# nodemcu.net
KiCad netlist of a schematic drawn in EAGLE
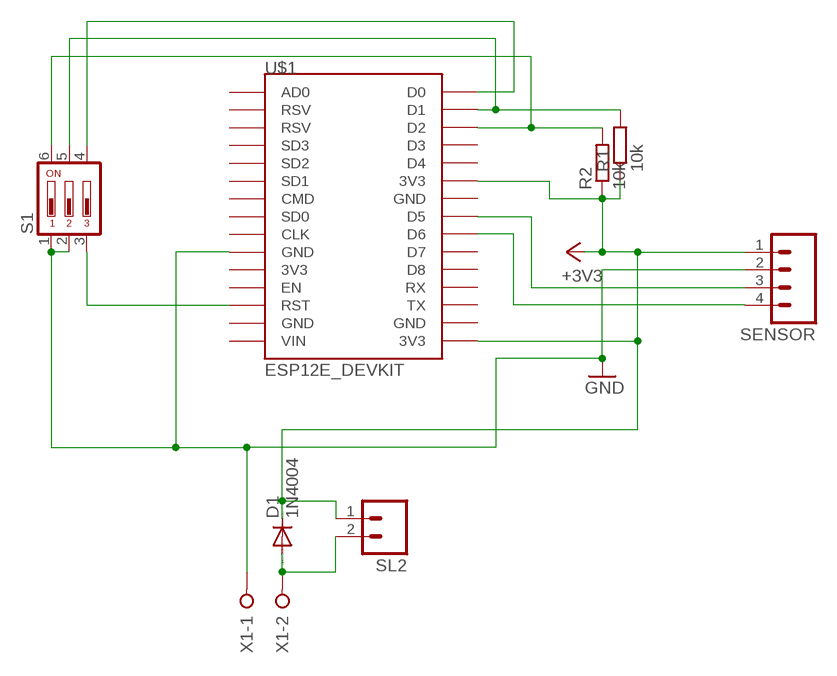
[diagram p0: schematic, sheet 1]

(export (version "E")
  (design (tool "Eeschema 10.0.6"))
  (components
    (comp (ref "D1")
      (value "1N4004")
      (footprint "eagle-import:DO41-10")
      (libsource (lib "eagle-import") (part "1N4004"))
    )
    (comp (ref "R1")
      (value "10k")
      (footprint "eagle-import:0207_10")
      (libsource (lib "eagle-import") (part "R-EU_0207/10"))
    )
    (comp (ref "R2")
      (value "10k")
      (footprint "eagle-import:0207_10")
      (libsource (lib "eagle-import") (part "R-EU_0207/10"))
    )
    (comp (ref "S1")
      (value "DIP03YL")
      (footprint "eagle-import:DIP03YL")
      (libsource (lib "eagle-import") (part "DIP03YL"))
    )
    (comp (ref "SENSOR")
      (value "M04")
      (footprint "eagle-import:04P")
      (libsource (lib "eagle-import") (part "M04"))
    )
    (comp (ref "SL2")
      (value "M02")
      (footprint "eagle-import:02P")
      (libsource (lib "eagle-import") (part "M02"))
    )
    (comp (ref "U$1")
      (value "ESP12E_DEVKIT")
      (footprint "eagle-import:ESP12E_DEVKIT")
      (libsource (lib "eagle-import") (part "ESP12E_DEVKIT"))
    )
    (comp (ref "X1")
      (value "W237-02P")
      (footprint "eagle-import:W237-132")
      (libsource (lib "eagle-import") (part "W237-02P"))
    )
  )
  (nets
    (net (code "1") (name "+3V3") (class "Default")
      (node (ref "D1") (pin "C") (pinfunction "C_C") (pintype "passive"))
      (node (ref "R1") (pin "1") (pinfunction "1_1") (pintype "passive"))
      (node (ref "R2") (pin "1") (pinfunction "1_1") (pintype "passive"))
      (node (ref "SENSOR") (pin "1") (pinfunction "1_1") (pintype "passive"))
      (node (ref "SL2") (pin "1") (pinfunction "1_1") (pintype "passive"))
      (node (ref "U$1") (pin "3V3@1") (pinfunction "3V3_3V3@1") (pintype "bidirectional"))
      (node (ref "U$1") (pin "3V3@2") (pinfunction "3V3_3V3@2") (pintype "bidirectional"))
    )
    (net (code "2") (name "GND") (class "Default")
      (node (ref "S1") (pin "1") (pinfunction "1_1") (pintype "passive"))
      (node (ref "S1") (pin "2") (pinfunction "2_2") (pintype "passive"))
      (node (ref "SENSOR") (pin "2") (pinfunction "2_2") (pintype "passive"))
      (node (ref "U$1") (pin "GND@0") (pinfunction "GND_GND@0") (pintype "bidirectional"))
      (node (ref "X1") (pin "1") (pinfunction "KL_1") (pintype "passive"))
    )
    (net (code "3") (name "Net-(R1-Pad2)") (class "Default")
      (node (ref "R1") (pin "2") (pinfunction "2_2") (pintype "passive"))
      (node (ref "S1") (pin "5") (pinfunction "5_5") (pintype "passive"))
      (node (ref "U$1") (pin "D1") (pinfunction "D1_D1") (pintype "bidirectional"))
    )
    (net (code "4") (name "Net-(R2-Pad2)") (class "Default")
      (node (ref "R2") (pin "2") (pinfunction "2_2") (pintype "passive"))
      (node (ref "S1") (pin "6") (pinfunction "6_6") (pintype "passive"))
      (node (ref "U$1") (pin "D2") (pinfunction "D2_D2") (pintype "bidirectional"))
    )
    (net (code "5") (name "Net-(S1-Pad3)") (class "Default")
      (node (ref "S1") (pin "3") (pinfunction "3_3") (pintype "passive"))
      (node (ref "U$1") (pin "RST") (pinfunction "RST_RST") (pintype "bidirectional"))
    )
    (net (code "6") (name "Net-(S1-Pad4)") (class "Default")
      (node (ref "S1") (pin "4") (pinfunction "4_4") (pintype "passive"))
      (node (ref "U$1") (pin "D0") (pinfunction "D0_D0") (pintype "bidirectional"))
    )
    (net (code "7") (name "Net-(SENSOR-Pad3)") (class "Default")
      (node (ref "SENSOR") (pin "3") (pinfunction "3_3") (pintype "passive"))
      (node (ref "U$1") (pin "D5") (pinfunction "D5_D5") (pintype "bidirectional"))
    )
    (net (code "8") (name "Net-(SENSOR-Pad4)") (class "Default")
      (node (ref "SENSOR") (pin "4") (pinfunction "4_4") (pintype "passive"))
      (node (ref "U$1") (pin "D6") (pinfunction "D6_D6") (pintype "bidirectional"))
    )
    (net (code "9") (name "Net-(X1B-KL)") (class "Default")
      (node (ref "D1") (pin "A") (pinfunction "A_A") (pintype "passive"))
      (node (ref "SL2") (pin "2") (pinfunction "2_2") (pintype "passive"))
      (node (ref "X1") (pin "2") (pinfunction "KL_2") (pintype "passive"))
    )
    (net (code "10") (name "unconnected-(U$1-3V3-Pad3V3@0)") (class "Default")
      (node (ref "U$1") (pin "3V3@0") (pinfunction "3V3_3V3@0") (pintype "bidirectional"))
    )
    (net (code "11") (name "unconnected-(U$1-GND-PadGND@1)") (class "Default")
      (node (ref "U$1") (pin "GND@1") (pinfunction "GND_GND@1") (pintype "bidirectional"))
    )
    (net (code "12") (name "unconnected-(U$1-GND-PadGND@2)") (class "Default")
      (node (ref "U$1") (pin "GND@2") (pinfunction "GND_GND@2") (pintype "bidirectional"))
    )
    (net (code "13") (name "unconnected-(U$1-GND-PadGND@3)") (class "Default")
      (node (ref "U$1") (pin "GND@3") (pinfunction "GND_GND@3") (pintype "bidirectional"))
    )
    (net (code "14") (name "unconnected-(U$1-PadAD0)") (class "Default")
      (node (ref "U$1") (pin "AD0") (pinfunction "AD0_AD0") (pintype "bidirectional"))
    )
    (net (code "15") (name "unconnected-(U$1-PadCLK)") (class "Default")
      (node (ref "U$1") (pin "CLK") (pinfunction "CLK_CLK") (pintype "bidirectional"))
    )
    (net (code "16") (name "unconnected-(U$1-PadCMD)") (class "Default")
      (node (ref "U$1") (pin "CMD") (pinfunction "CMD_CMD") (pintype "bidirectional"))
    )
    (net (code "17") (name "unconnected-(U$1-PadD3)") (class "Default")
      (node (ref "U$1") (pin "D3") (pinfunction "D3_D3") (pintype "bidirectional"))
    )
    (net (code "18") (name "unconnected-(U$1-PadD4)") (class "Default")
      (node (ref "U$1") (pin "D4") (pinfunction "D4_D4") (pintype "bidirectional"))
    )
    (net (code "19") (name "unconnected-(U$1-PadD7)") (class "Default")
      (node (ref "U$1") (pin "D7") (pinfunction "D7_D7") (pintype "bidirectional"))
    )
    (net (code "20") (name "unconnected-(U$1-PadD8)") (class "Default")
      (node (ref "U$1") (pin "D8") (pinfunction "D8_D8") (pintype "bidirectional"))
    )
    (net (code "21") (name "unconnected-(U$1-PadEN)") (class "Default")
      (node (ref "U$1") (pin "EN") (pinfunction "EN_EN") (pintype "bidirectional"))
    )
    (net (code "22") (name "unconnected-(U$1-PadRX)") (class "Default")
      (node (ref "U$1") (pin "RX") (pinfunction "RX_RX") (pintype "bidirectional"))
    )
    (net (code "23") (name "unconnected-(U$1-PadSD0)") (class "Default")
      (node (ref "U$1") (pin "SD0") (pinfunction "SD0_SD0") (pintype "bidirectional"))
    )
    (net (code "24") (name "unconnected-(U$1-PadSD1)") (class "Default")
      (node (ref "U$1") (pin "SD1") (pinfunction "SD1_SD1") (pintype "bidirectional"))
    )
    (net (code "25") (name "unconnected-(U$1-PadSD2)") (class "Default")
      (node (ref "U$1") (pin "SD2") (pinfunction "SD2_SD2") (pintype "bidirectional"))
    )
    (net (code "26") (name "unconnected-(U$1-PadSD3)") (class "Default")
      (node (ref "U$1") (pin "SD3") (pinfunction "SD3_SD3") (pintype "bidirectional"))
    )
    (net (code "27") (name "unconnected-(U$1-PadTX)") (class "Default")
      (node (ref "U$1") (pin "TX") (pinfunction "TX_TX") (pintype "bidirectional"))
    )
    (net (code "28") (name "unconnected-(U$1-PadVIN)") (class "Default")
      (node (ref "U$1") (pin "VIN") (pinfunction "VIN_VIN") (pintype "bidirectional"))
    )
    (net (code "29") (name "unconnected-(U$1-RSV-PadRSV@0)") (class "Default")
      (node (ref "U$1") (pin "RSV@0") (pinfunction "RSV_RSV@0") (pintype "bidirectional"))
    )
    (net (code "30") (name "unconnected-(U$1-RSV-PadRSV@1)") (class "Default")
      (node (ref "U$1") (pin "RSV@1") (pinfunction "RSV_RSV@1") (pintype "bidirectional"))
    )
  )
)
